# Me507Project.net
KiCad netlist of a schematic drawn in EAGLE
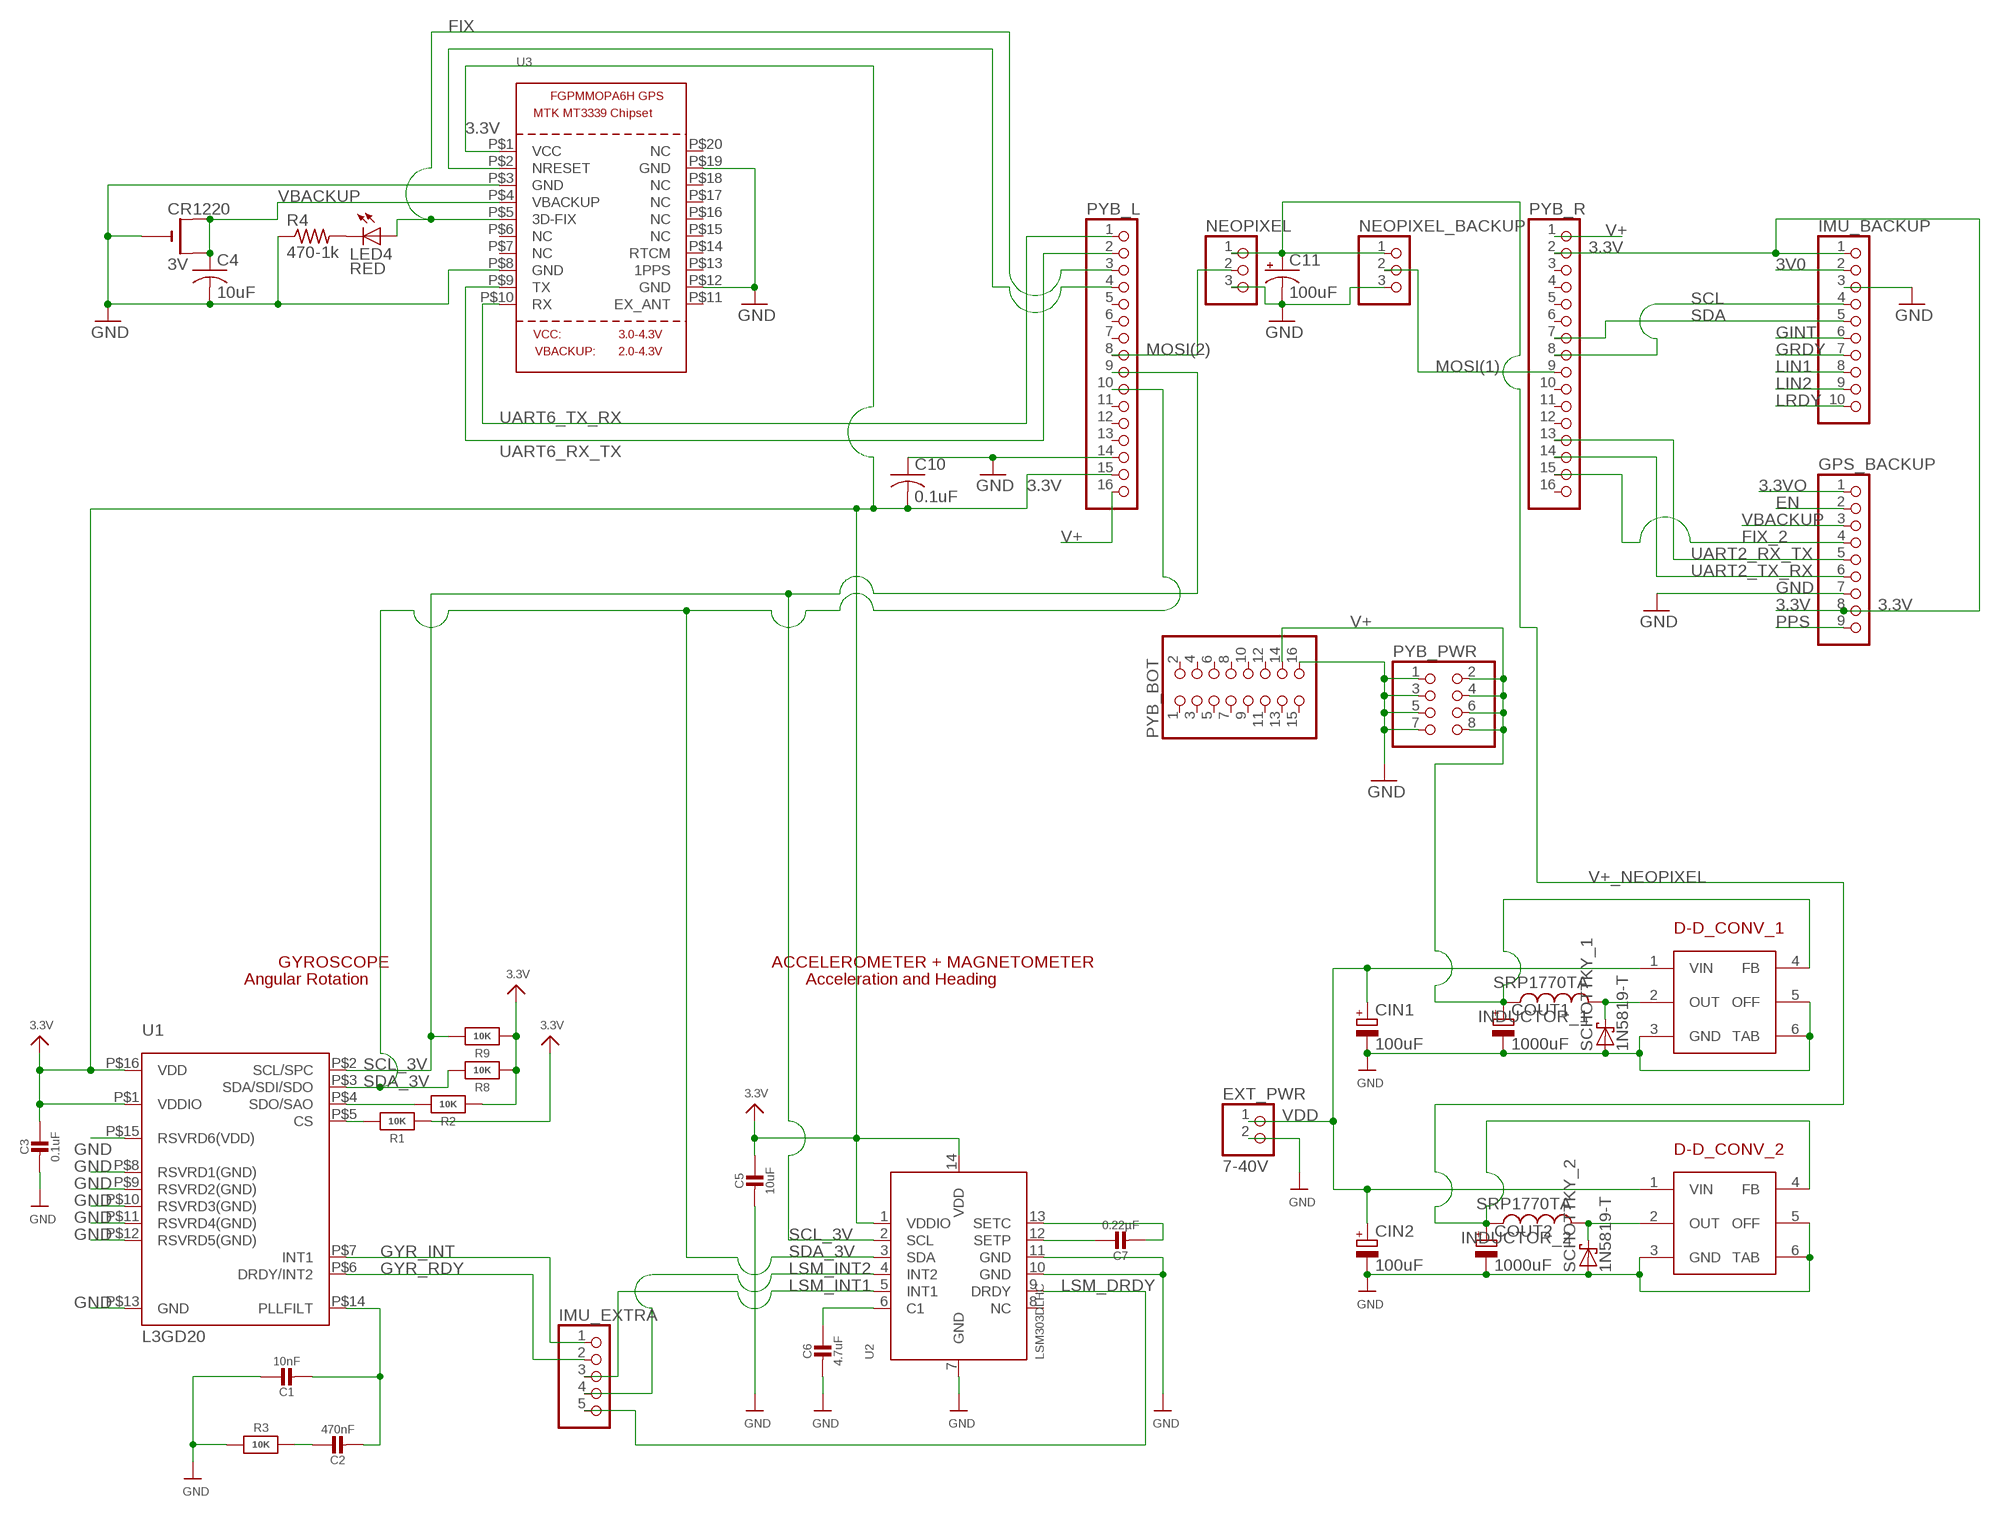
[diagram p0: schematic, sheet 1]

(export (version "E")
  (design (tool "Eeschema 10.0.6"))
  (components
    (comp (ref "C1")
      (value "10nF")
      (footprint "eagle-import:_0805MP")
      (libsource (lib "eagle-import") (part "CAP_CERAMIC_0805MP"))
    )
    (comp (ref "C2")
      (value "470nF")
      (footprint "eagle-import:_0805MP")
      (libsource (lib "eagle-import") (part "CAP_CERAMIC_0805MP"))
    )
    (comp (ref "C3")
      (value "0.1uF")
      (footprint "eagle-import:_0805MP")
      (libsource (lib "eagle-import") (part "CAP_CERAMIC_0805MP"))
    )
    (comp (ref "C4")
      (value "10uF")
      (footprint "eagle-import:C0805K")
      (libsource (lib "eagle-import") (part "C-USC0805K"))
    )
    (comp (ref "C5")
      (value "10uF")
      (footprint "eagle-import:_0805MP")
      (libsource (lib "eagle-import") (part "CAP_CERAMIC_0805MP"))
    )
    (comp (ref "C6")
      (value "4.7uF")
      (footprint "eagle-import:_0805MP")
      (libsource (lib "eagle-import") (part "CAP_CERAMIC_0805MP"))
    )
    (comp (ref "C7")
      (value "0.22µF")
      (footprint "eagle-import:_0805MP")
      (libsource (lib "eagle-import") (part "CAP_CERAMIC_0805MP"))
    )
    (comp (ref "C10")
      (value "0.1uF")
      (footprint "eagle-import:C0805K")
      (libsource (lib "eagle-import") (part "C-USC0805K"))
    )
    (comp (ref "C11")
      (value "100uF")
      (footprint "eagle-import:153CLV-0810")
      (libsource (lib "eagle-import") (part "CPOL-US153CLV-0810"))
    )
    (comp (ref "CIN1")
      (value "100uF")
      (footprint "eagle-import:UD-8X10_NICHICON")
      (libsource (lib "eagle-import") (part "CPOL-EUUD-8X10"))
    )
    (comp (ref "CIN2")
      (value "100uF")
      (footprint "eagle-import:UD-8X10_NICHICON")
      (libsource (lib "eagle-import") (part "CPOL-EUUD-8X10"))
    )
    (comp (ref "COUT1")
      (value "1000uF")
      (footprint "eagle-import:E5-13")
      (libsource (lib "eagle-import") (part "CPOL-EUE5-13"))
    )
    (comp (ref "COUT2")
      (value "1000uF")
      (footprint "eagle-import:E5-13")
      (libsource (lib "eagle-import") (part "CPOL-EUE5-13"))
    )
    (comp (ref "CR1220")
      (value "3V")
      (footprint "eagle-import:CR1220-SMD")
      (libsource (lib "eagle-import") (part "CR1220SMT"))
    )
    (comp (ref "D-D_CONV_1")
      (value "AP3003")
      (footprint "eagle-import:TO263-5")
      (libsource (lib "eagle-import") (part "AP3003"))
    )
    (comp (ref "D-D_CONV_2")
      (value "AP3003")
      (footprint "eagle-import:TO263-5")
      (libsource (lib "eagle-import") (part "AP3003"))
    )
    (comp (ref "EXT_PWR")
      (value "7-40V")
      (footprint "eagle-import:1X02")
      (libsource (lib "eagle-import") (part "PINHD-1X2"))
    )
    (comp (ref "GPS_BACKUP")
      (value "PINHD-1X9")
      (footprint "eagle-import:1X09")
      (libsource (lib "eagle-import") (part "PINHD-1X9"))
    )
    (comp (ref "IMU_BACKUP")
      (value "PINHD-1X10")
      (footprint "eagle-import:1X10")
      (libsource (lib "eagle-import") (part "PINHD-1X10"))
    )
    (comp (ref "IMU_EXTRA")
      (value "PINHD-1X5")
      (footprint "eagle-import:1X05")
      (libsource (lib "eagle-import") (part "PINHD-1X5"))
    )
    (comp (ref "INDUCTOR_1")
      (value "SRP1770TA")
      (footprint "eagle-import:SRP1770TA")
      (libsource (lib "eagle-import") (part "SRP1770TA"))
    )
    (comp (ref "INDUCTOR_2")
      (value "SRP1770TA")
      (footprint "eagle-import:SRP1770TA")
      (libsource (lib "eagle-import") (part "SRP1770TA"))
    )
    (comp (ref "LED4")
      (value "RED")
      (footprint "eagle-import:CHIP-LED0805")
      (libsource (lib "eagle-import") (part "LEDCHIP-LED0805"))
    )
    (comp (ref "NEOPIXEL")
      (value "PINHD-1X3")
      (footprint "eagle-import:1X03")
      (libsource (lib "eagle-import") (part "PINHD-1X3"))
    )
    (comp (ref "NEOPIXEL_BACKUP")
      (value "PINHD-1X3")
      (footprint "eagle-import:1X03")
      (libsource (lib "eagle-import") (part "PINHD-1X3"))
    )
    (comp (ref "PYB_BOT")
      (value "PINHD-2X8")
      (footprint "eagle-import:2X08")
      (libsource (lib "eagle-import") (part "PINHD-2X8"))
    )
    (comp (ref "PYB_L")
      (value "PINHD-1X16")
      (footprint "eagle-import:1X16")
      (libsource (lib "eagle-import") (part "PINHD-1X16"))
    )
    (comp (ref "PYB_PWR")
      (value "PINHD-2X4")
      (footprint "eagle-import:2X04")
      (libsource (lib "eagle-import") (part "PINHD-2X4"))
    )
    (comp (ref "PYB_R")
      (value "PINHD-1X16")
      (footprint "eagle-import:1X16")
      (libsource (lib "eagle-import") (part "PINHD-1X16"))
    )
    (comp (ref "R1")
      (value "10K")
      (footprint "eagle-import:_0805MP")
      (libsource (lib "eagle-import") (part "RESISTOR_0805MP"))
    )
    (comp (ref "R2")
      (value "10K")
      (footprint "eagle-import:_0805MP")
      (libsource (lib "eagle-import") (part "RESISTOR_0805MP"))
    )
    (comp (ref "R3")
      (value "10K")
      (footprint "eagle-import:_0805MP")
      (libsource (lib "eagle-import") (part "RESISTOR_0805MP"))
    )
    (comp (ref "R4")
      (value "470-1k")
      (footprint "eagle-import:R0805")
      (libsource (lib "eagle-import") (part "R-US_R0805"))
    )
    (comp (ref "R8")
      (value "10K")
      (footprint "eagle-import:_0805MP")
      (libsource (lib "eagle-import") (part "RESISTOR_0805MP"))
    )
    (comp (ref "R9")
      (value "10K")
      (footprint "eagle-import:_0805MP")
      (libsource (lib "eagle-import") (part "RESISTOR_0805MP"))
    )
    (comp (ref "SCHOTTKY_1")
      (value "1N5819-T")
      (footprint "eagle-import:DO41-7.6")
      (libsource (lib "eagle-import") (part "1N5819-T"))
    )
    (comp (ref "SCHOTTKY_2")
      (value "1N5819-T")
      (footprint "eagle-import:DO41-7.6")
      (libsource (lib "eagle-import") (part "1N5819-T"))
    )
    (comp (ref "U1")
      (value "L3GD20")
      (footprint "eagle-import:L3G4200D_LGA16L")
      (libsource (lib "eagle-import") (part "GYRO_L3G2400D"))
    )
    (comp (ref "U2")
      (value "LSM303DLHC")
      (footprint "eagle-import:LGA14")
      (libsource (lib "eagle-import") (part "LSM303DLHC"))
    )
    (comp (ref "U3")
      (value "GPS_FGPMMOPA6H")
      (footprint "eagle-import:FGPMMOPA6H")
      (libsource (lib "eagle-import") (part "GPS_FGPMMOPA6H"))
    )
  )
  (nets
    (net (code "1") (name "/3.3VO") (class "Default")
      (node (ref "GPS_BACKUP") (pin "1") (pinfunction "1_1") (pintype "passive"))
    )
    (net (code "2") (name "/3V0") (class "Default")
      (node (ref "IMU_BACKUP") (pin "2") (pinfunction "2_2") (pintype "passive"))
    )
    (net (code "3") (name "/EN") (class "Default")
      (node (ref "GPS_BACKUP") (pin "2") (pinfunction "2_2") (pintype "passive"))
    )
    (net (code "4") (name "/FIX") (class "Default")
      (node (ref "LED4") (pin "A") (pinfunction "A_A") (pintype "passive"))
      (node (ref "PYB_L") (pin "3") (pinfunction "3_3") (pintype "passive"))
      (node (ref "U3") (pin "P$5") (pinfunction "3D-FIX_P$5") (pintype "bidirectional"))
    )
    (net (code "5") (name "/FIX_2") (class "Default")
      (node (ref "GPS_BACKUP") (pin "4") (pinfunction "4_4") (pintype "passive"))
      (node (ref "PYB_R") (pin "15") (pinfunction "15_15") (pintype "passive"))
    )
    (net (code "6") (name "/GINT") (class "Default")
      (node (ref "IMU_BACKUP") (pin "6") (pinfunction "6_6") (pintype "passive"))
    )
    (net (code "7") (name "/GRDY") (class "Default")
      (node (ref "IMU_BACKUP") (pin "7") (pinfunction "7_7") (pintype "passive"))
    )
    (net (code "8") (name "/GYR_INT") (class "Default")
      (node (ref "IMU_EXTRA") (pin "1") (pinfunction "1_1") (pintype "passive"))
      (node (ref "U1") (pin "P$7") (pinfunction "INT1_P$7") (pintype "bidirectional"))
    )
    (net (code "9") (name "/GYR_RDY") (class "Default")
      (node (ref "IMU_EXTRA") (pin "2") (pinfunction "2_2") (pintype "passive"))
      (node (ref "U1") (pin "P$6") (pinfunction "DRDY/INT2_P$6") (pintype "bidirectional"))
    )
    (net (code "10") (name "/LIN1") (class "Default")
      (node (ref "IMU_BACKUP") (pin "8") (pinfunction "8_8") (pintype "passive"))
    )
    (net (code "11") (name "/LIN2") (class "Default")
      (node (ref "IMU_BACKUP") (pin "9") (pinfunction "9_9") (pintype "passive"))
    )
    (net (code "12") (name "/LRDY") (class "Default")
      (node (ref "IMU_BACKUP") (pin "10") (pinfunction "10_10") (pintype "passive"))
    )
    (net (code "13") (name "/LSM_DRDY") (class "Default")
      (node (ref "IMU_EXTRA") (pin "5") (pinfunction "5_5") (pintype "passive"))
      (node (ref "U2") (pin "9") (pinfunction "DRDY_9") (pintype "output"))
    )
    (net (code "14") (name "/LSM_INT1") (class "Default")
      (node (ref "IMU_EXTRA") (pin "3") (pinfunction "3_3") (pintype "passive"))
      (node (ref "U2") (pin "5") (pinfunction "INT1_5") (pintype "output"))
    )
    (net (code "15") (name "/LSM_INT2") (class "Default")
      (node (ref "IMU_EXTRA") (pin "4") (pinfunction "4_4") (pintype "passive"))
      (node (ref "U2") (pin "4") (pinfunction "INT2_4") (pintype "output"))
    )
    (net (code "16") (name "/MOSI(1)") (class "Default")
      (node (ref "NEOPIXEL_BACKUP") (pin "2") (pinfunction "2_2") (pintype "passive"))
      (node (ref "PYB_R") (pin "9") (pinfunction "9_9") (pintype "passive"))
    )
    (net (code "17") (name "/MOSI(2)") (class "Default")
      (node (ref "NEOPIXEL") (pin "2") (pinfunction "2_2") (pintype "passive"))
      (node (ref "PYB_L") (pin "8") (pinfunction "8_8") (pintype "passive"))
    )
    (net (code "18") (name "/PPS") (class "Default")
      (node (ref "GPS_BACKUP") (pin "9") (pinfunction "9_9") (pintype "passive"))
    )
    (net (code "19") (name "/SCL") (class "Default")
      (node (ref "IMU_BACKUP") (pin "4") (pinfunction "4_4") (pintype "passive"))
      (node (ref "PYB_R") (pin "8") (pinfunction "8_8") (pintype "passive"))
    )
    (net (code "20") (name "/SCL_3V") (class "Default")
      (node (ref "PYB_L") (pin "9") (pinfunction "9_9") (pintype "passive"))
      (node (ref "R9") (pin "2") (pinfunction "2_2") (pintype "passive"))
      (node (ref "U1") (pin "P$2") (pinfunction "SCL/SPC_P$2") (pintype "bidirectional"))
      (node (ref "U2") (pin "2") (pinfunction "SCL_2") (pintype "bidirectional"))
    )
    (net (code "21") (name "/SDA") (class "Default")
      (node (ref "IMU_BACKUP") (pin "5") (pinfunction "5_5") (pintype "passive"))
      (node (ref "PYB_R") (pin "7") (pinfunction "7_7") (pintype "passive"))
    )
    (net (code "22") (name "/SDA_3V") (class "Default")
      (node (ref "PYB_L") (pin "10") (pinfunction "10_10") (pintype "passive"))
      (node (ref "R8") (pin "2") (pinfunction "2_2") (pintype "passive"))
      (node (ref "U1") (pin "P$3") (pinfunction "SDA/SDI/SDO_P$3") (pintype "bidirectional"))
      (node (ref "U2") (pin "3") (pinfunction "SDA_3") (pintype "bidirectional"))
    )
    (net (code "23") (name "/UART2_RX_TX") (class "Default")
      (node (ref "GPS_BACKUP") (pin "5") (pinfunction "5_5") (pintype "passive"))
      (node (ref "PYB_R") (pin "13") (pinfunction "13_13") (pintype "passive"))
    )
    (net (code "24") (name "/UART2_TX_RX") (class "Default")
      (node (ref "GPS_BACKUP") (pin "6") (pinfunction "6_6") (pintype "passive"))
      (node (ref "PYB_R") (pin "14") (pinfunction "14_14") (pintype "passive"))
    )
    (net (code "25") (name "/UART6_RX_TX") (class "Default")
      (node (ref "PYB_L") (pin "2") (pinfunction "2_2") (pintype "passive"))
      (node (ref "U3") (pin "P$9") (pinfunction "TX_P$9") (pintype "bidirectional"))
    )
    (net (code "26") (name "/UART6_TX_RX") (class "Default")
      (node (ref "PYB_L") (pin "1") (pinfunction "1_1") (pintype "passive"))
      (node (ref "U3") (pin "P$10") (pinfunction "RX_P$10") (pintype "bidirectional"))
    )
    (net (code "27") (name "/V+") (class "Default")
      (node (ref "COUT1") (pin "+") (pinfunction "+_+") (pintype "passive"))
      (node (ref "D-D_CONV_1") (pin "4") (pinfunction "FB_4") (pintype "bidirectional"))
      (node (ref "INDUCTOR_1") (pin "P$3") (pinfunction "1_P$3") (pintype "passive"))
      (node (ref "PYB_BOT") (pin "14") (pinfunction "14_14") (pintype "passive"))
      (node (ref "PYB_L") (pin "16") (pinfunction "16_16") (pintype "passive"))
      (node (ref "PYB_PWR") (pin "2") (pinfunction "2_2") (pintype "passive"))
      (node (ref "PYB_PWR") (pin "4") (pinfunction "4_4") (pintype "passive"))
      (node (ref "PYB_PWR") (pin "6") (pinfunction "6_6") (pintype "passive"))
      (node (ref "PYB_PWR") (pin "8") (pinfunction "8_8") (pintype "passive"))
      (node (ref "PYB_R") (pin "1") (pinfunction "1_1") (pintype "passive"))
    )
    (net (code "28") (name "/V+_NEOPIXEL") (class "Default")
      (node (ref "C11") (pin "+") (pinfunction "+_+") (pintype "passive"))
      (node (ref "COUT2") (pin "+") (pinfunction "+_+") (pintype "passive"))
      (node (ref "D-D_CONV_2") (pin "4") (pinfunction "FB_4") (pintype "bidirectional"))
      (node (ref "INDUCTOR_2") (pin "P$3") (pinfunction "1_P$3") (pintype "passive"))
      (node (ref "NEOPIXEL") (pin "1") (pinfunction "1_1") (pintype "passive"))
      (node (ref "NEOPIXEL_BACKUP") (pin "1") (pinfunction "1_1") (pintype "passive"))
    )
    (net (code "29") (name "/VBACKUP") (class "Default")
      (node (ref "C4") (pin "1") (pinfunction "1_1") (pintype "passive"))
      (node (ref "CR1220") (pin "+$1") (pinfunction "+_+$1") (pintype "passive"))
      (node (ref "CR1220") (pin "+$2") (pinfunction "+1_+$2") (pintype "passive"))
      (node (ref "GPS_BACKUP") (pin "3") (pinfunction "3_3") (pintype "passive"))
      (node (ref "U3") (pin "P$4") (pinfunction "VBACKUP_P$4") (pintype "bidirectional"))
    )
    (net (code "30") (name "/VDD") (class "Default")
      (node (ref "CIN1") (pin "+") (pinfunction "+_+") (pintype "passive"))
      (node (ref "CIN2") (pin "+") (pinfunction "+_+") (pintype "passive"))
      (node (ref "D-D_CONV_1") (pin "1") (pinfunction "VIN_1") (pintype "bidirectional"))
      (node (ref "D-D_CONV_2") (pin "1") (pinfunction "VIN_1") (pintype "bidirectional"))
      (node (ref "EXT_PWR") (pin "1") (pinfunction "1_1") (pintype "passive"))
    )
    (net (code "31") (name "3.3V") (class "Default")
      (node (ref "C10") (pin "2") (pinfunction "2_2") (pintype "passive"))
      (node (ref "C3") (pin "1") (pinfunction "1_1") (pintype "passive"))
      (node (ref "C5") (pin "1") (pinfunction "1_1") (pintype "passive"))
      (node (ref "GPS_BACKUP") (pin "8") (pinfunction "8_8") (pintype "passive"))
      (node (ref "IMU_BACKUP") (pin "1") (pinfunction "1_1") (pintype "passive"))
      (node (ref "PYB_L") (pin "15") (pinfunction "15_15") (pintype "passive"))
      (node (ref "PYB_R") (pin "2") (pinfunction "2_2") (pintype "passive"))
      (node (ref "R1") (pin "1") (pinfunction "1_1") (pintype "passive"))
      (node (ref "R2") (pin "1") (pinfunction "1_1") (pintype "passive"))
      (node (ref "R8") (pin "1") (pinfunction "1_1") (pintype "passive"))
      (node (ref "R9") (pin "1") (pinfunction "1_1") (pintype "passive"))
      (node (ref "U1") (pin "P$1") (pinfunction "VDDIO_P$1") (pintype "power_in"))
      (node (ref "U1") (pin "P$16") (pinfunction "VDD_P$16") (pintype "bidirectional"))
      (node (ref "U2") (pin "1") (pinfunction "VDDIO_1") (pintype "power_in"))
      (node (ref "U2") (pin "14") (pinfunction "VDD_14") (pintype "power_in"))
      (node (ref "U3") (pin "P$1") (pinfunction "VCC_P$1") (pintype "bidirectional"))
    )
    (net (code "32") (name "GND") (class "Default")
      (node (ref "C1") (pin "1") (pinfunction "1_1") (pintype "passive"))
      (node (ref "C10") (pin "1") (pinfunction "1_1") (pintype "passive"))
      (node (ref "C11") (pin "-") (pinfunction "-_-") (pintype "passive"))
      (node (ref "C3") (pin "2") (pinfunction "2_2") (pintype "passive"))
      (node (ref "C4") (pin "2") (pinfunction "2_2") (pintype "passive"))
      (node (ref "C5") (pin "2") (pinfunction "2_2") (pintype "passive"))
      (node (ref "C6") (pin "2") (pinfunction "2_2") (pintype "passive"))
      (node (ref "CIN1") (pin "-") (pinfunction "-_-") (pintype "passive"))
      (node (ref "CIN2") (pin "-") (pinfunction "-_-") (pintype "passive"))
      (node (ref "COUT1") (pin "-") (pinfunction "-_-") (pintype "passive"))
      (node (ref "COUT2") (pin "-") (pinfunction "-_-") (pintype "passive"))
      (node (ref "CR1220") (pin "-") (pinfunction "-_-") (pintype "passive"))
      (node (ref "D-D_CONV_1") (pin "3") (pinfunction "GND_3") (pintype "bidirectional"))
      (node (ref "D-D_CONV_1") (pin "5") (pinfunction "OFF_5") (pintype "bidirectional"))
      (node (ref "D-D_CONV_1") (pin "6") (pinfunction "TAB_6") (pintype "bidirectional"))
      (node (ref "D-D_CONV_2") (pin "3") (pinfunction "GND_3") (pintype "bidirectional"))
      (node (ref "D-D_CONV_2") (pin "5") (pinfunction "OFF_5") (pintype "bidirectional"))
      (node (ref "D-D_CONV_2") (pin "6") (pinfunction "TAB_6") (pintype "bidirectional"))
      (node (ref "EXT_PWR") (pin "2") (pinfunction "2_2") (pintype "passive"))
      (node (ref "GPS_BACKUP") (pin "7") (pinfunction "7_7") (pintype "passive"))
      (node (ref "IMU_BACKUP") (pin "3") (pinfunction "3_3") (pintype "passive"))
      (node (ref "NEOPIXEL") (pin "3") (pinfunction "3_3") (pintype "passive"))
      (node (ref "NEOPIXEL_BACKUP") (pin "3") (pinfunction "3_3") (pintype "passive"))
      (node (ref "PYB_BOT") (pin "16") (pinfunction "16_16") (pintype "passive"))
      (node (ref "PYB_L") (pin "14") (pinfunction "14_14") (pintype "passive"))
      (node (ref "PYB_PWR") (pin "1") (pinfunction "1_1") (pintype "passive"))
      (node (ref "PYB_PWR") (pin "3") (pinfunction "3_3") (pintype "passive"))
      (node (ref "PYB_PWR") (pin "5") (pinfunction "5_5") (pintype "passive"))
      (node (ref "PYB_PWR") (pin "7") (pinfunction "7_7") (pintype "passive"))
      (node (ref "R3") (pin "1") (pinfunction "1_1") (pintype "passive"))
      (node (ref "R4") (pin "1") (pinfunction "1_1") (pintype "passive"))
      (node (ref "SCHOTTKY_1") (pin "A") (pinfunction "A_A") (pintype "passive"))
      (node (ref "SCHOTTKY_2") (pin "A") (pinfunction "A_A") (pintype "passive"))
      (node (ref "U1") (pin "P$10") (pinfunction "RSVRD3(GND)_P$10") (pintype "bidirectional"))
      (node (ref "U1") (pin "P$11") (pinfunction "RSVRD4(GND)_P$11") (pintype "bidirectional"))
      (node (ref "U1") (pin "P$12") (pinfunction "RSVRD5(GND)_P$12") (pintype "bidirectional"))
      (node (ref "U1") (pin "P$13") (pinfunction "GND_P$13") (pintype "bidirectional"))
      (node (ref "U1") (pin "P$15") (pinfunction "RSVRD6(VDD)_P$15") (pintype "bidirectional"))
      (node (ref "U1") (pin "P$8") (pinfunction "RSVRD1(GND)_P$8") (pintype "bidirectional"))
      (node (ref "U1") (pin "P$9") (pinfunction "RSVRD2(GND)_P$9") (pintype "bidirectional"))
      (node (ref "U2") (pin "10") (pinfunction "GND_10") (pintype "power_in"))
      (node (ref "U2") (pin "11") (pinfunction "GND_11") (pintype "power_in"))
      (node (ref "U2") (pin "7") (pinfunction "GND_7") (pintype "power_in"))
      (node (ref "U3") (pin "P$12") (pinfunction "GND_P$12") (pintype "bidirectional"))
      (node (ref "U3") (pin "P$19") (pinfunction "GND_P$19") (pintype "bidirectional"))
      (node (ref "U3") (pin "P$3") (pinfunction "GND_P$3") (pintype "bidirectional"))
      (node (ref "U3") (pin "P$8") (pinfunction "GND_P$8") (pintype "bidirectional"))
    )
    (net (code "33") (name "Net-(C2-Pad1)") (class "Default")
      (node (ref "C2") (pin "1") (pinfunction "1_1") (pintype "passive"))
      (node (ref "R3") (pin "2") (pinfunction "2_2") (pintype "passive"))
    )
    (net (code "34") (name "Net-(D-D_CONV_1-OUT)") (class "Default")
      (node (ref "D-D_CONV_1") (pin "2") (pinfunction "OUT_2") (pintype "bidirectional"))
      (node (ref "INDUCTOR_1") (pin "P$4") (pinfunction "2_P$4") (pintype "passive"))
      (node (ref "SCHOTTKY_1") (pin "C") (pinfunction "C_C") (pintype "passive"))
    )
    (net (code "35") (name "Net-(D-D_CONV_2-OUT)") (class "Default")
      (node (ref "D-D_CONV_2") (pin "2") (pinfunction "OUT_2") (pintype "bidirectional"))
      (node (ref "INDUCTOR_2") (pin "P$4") (pinfunction "2_P$4") (pintype "passive"))
      (node (ref "SCHOTTKY_2") (pin "C") (pinfunction "C_C") (pintype "passive"))
    )
    (net (code "36") (name "Net-(LED4-PadC)") (class "Default")
      (node (ref "LED4") (pin "C") (pinfunction "C_C") (pintype "passive"))
      (node (ref "R4") (pin "2") (pinfunction "2_2") (pintype "passive"))
    )
    (net (code "37") (name "Net-(U1-CS)") (class "Default")
      (node (ref "R1") (pin "2") (pinfunction "2_2") (pintype "passive"))
      (node (ref "U1") (pin "P$5") (pinfunction "CS_P$5") (pintype "bidirectional"))
    )
    (net (code "38") (name "Net-(U1-PLLFILT)") (class "Default")
      (node (ref "C1") (pin "2") (pinfunction "2_2") (pintype "passive"))
      (node (ref "C2") (pin "2") (pinfunction "2_2") (pintype "passive"))
      (node (ref "U1") (pin "P$14") (pinfunction "PLLFILT_P$14") (pintype "bidirectional"))
    )
    (net (code "39") (name "Net-(U1-SDO{slash}SAO)") (class "Default")
      (node (ref "R2") (pin "2") (pinfunction "2_2") (pintype "passive"))
      (node (ref "U1") (pin "P$4") (pinfunction "SDO/SAO_P$4") (pintype "bidirectional"))
    )
    (net (code "40") (name "Net-(U2-C1)") (class "Default")
      (node (ref "C6") (pin "1") (pinfunction "1_1") (pintype "passive"))
      (node (ref "U2") (pin "6") (pinfunction "C1_6") (pintype "bidirectional"))
    )
    (net (code "41") (name "Net-(U2-SETC)") (class "Default")
      (node (ref "C7") (pin "2") (pinfunction "2_2") (pintype "passive"))
      (node (ref "U2") (pin "13") (pinfunction "SETC_13") (pintype "bidirectional"))
    )
    (net (code "42") (name "Net-(U2-SETP)") (class "Default")
      (node (ref "C7") (pin "1") (pinfunction "1_1") (pintype "passive"))
      (node (ref "U2") (pin "12") (pinfunction "SETP_12") (pintype "bidirectional"))
    )
    (net (code "43") (name "Net-(U3-NRESET)") (class "Default")
      (node (ref "PYB_L") (pin "4") (pinfunction "4_4") (pintype "passive"))
      (node (ref "U3") (pin "P$2") (pinfunction "NRESET_P$2") (pintype "bidirectional"))
    )
    (net (code "44") (name "unconnected-(PYB_BOT-Pad1)") (class "Default")
      (node (ref "PYB_BOT") (pin "1") (pinfunction "1_1") (pintype "passive"))
    )
    (net (code "45") (name "unconnected-(PYB_BOT-Pad2)") (class "Default")
      (node (ref "PYB_BOT") (pin "2") (pinfunction "2_2") (pintype "passive"))
    )
    (net (code "46") (name "unconnected-(PYB_BOT-Pad3)") (class "Default")
      (node (ref "PYB_BOT") (pin "3") (pinfunction "3_3") (pintype "passive"))
    )
    (net (code "47") (name "unconnected-(PYB_BOT-Pad4)") (class "Default")
      (node (ref "PYB_BOT") (pin "4") (pinfunction "4_4") (pintype "passive"))
    )
    (net (code "48") (name "unconnected-(PYB_BOT-Pad5)") (class "Default")
      (node (ref "PYB_BOT") (pin "5") (pinfunction "5_5") (pintype "passive"))
    )
    (net (code "49") (name "unconnected-(PYB_BOT-Pad6)") (class "Default")
      (node (ref "PYB_BOT") (pin "6") (pinfunction "6_6") (pintype "passive"))
    )
    (net (code "50") (name "unconnected-(PYB_BOT-Pad7)") (class "Default")
      (node (ref "PYB_BOT") (pin "7") (pinfunction "7_7") (pintype "passive"))
    )
    (net (code "51") (name "unconnected-(PYB_BOT-Pad8)") (class "Default")
      (node (ref "PYB_BOT") (pin "8") (pinfunction "8_8") (pintype "passive"))
    )
    (net (code "52") (name "unconnected-(PYB_BOT-Pad9)") (class "Default")
      (node (ref "PYB_BOT") (pin "9") (pinfunction "9_9") (pintype "passive"))
    )
    (net (code "53") (name "unconnected-(PYB_BOT-Pad10)") (class "Default")
      (node (ref "PYB_BOT") (pin "10") (pinfunction "10_10") (pintype "passive"))
    )
    (net (code "54") (name "unconnected-(PYB_BOT-Pad11)") (class "Default")
      (node (ref "PYB_BOT") (pin "11") (pinfunction "11_11") (pintype "passive"))
    )
    (net (code "55") (name "unconnected-(PYB_BOT-Pad12)") (class "Default")
      (node (ref "PYB_BOT") (pin "12") (pinfunction "12_12") (pintype "passive"))
    )
    (net (code "56") (name "unconnected-(PYB_BOT-Pad13)") (class "Default")
      (node (ref "PYB_BOT") (pin "13") (pinfunction "13_13") (pintype "passive"))
    )
    (net (code "57") (name "unconnected-(PYB_BOT-Pad15)") (class "Default")
      (node (ref "PYB_BOT") (pin "15") (pinfunction "15_15") (pintype "passive"))
    )
    (net (code "58") (name "unconnected-(PYB_L-Pad5)") (class "Default")
      (node (ref "PYB_L") (pin "5") (pinfunction "5_5") (pintype "passive"))
    )
    (net (code "59") (name "unconnected-(PYB_L-Pad6)") (class "Default")
      (node (ref "PYB_L") (pin "6") (pinfunction "6_6") (pintype "passive"))
    )
    (net (code "60") (name "unconnected-(PYB_L-Pad7)") (class "Default")
      (node (ref "PYB_L") (pin "7") (pinfunction "7_7") (pintype "passive"))
    )
    (net (code "61") (name "unconnected-(PYB_L-Pad11)") (class "Default")
      (node (ref "PYB_L") (pin "11") (pinfunction "11_11") (pintype "passive"))
    )
    (net (code "62") (name "unconnected-(PYB_L-Pad12)") (class "Default")
      (node (ref "PYB_L") (pin "12") (pinfunction "12_12") (pintype "passive"))
    )
    (net (code "63") (name "unconnected-(PYB_L-Pad13)") (class "Default")
      (node (ref "PYB_L") (pin "13") (pinfunction "13_13") (pintype "passive"))
    )
    (net (code "64") (name "unconnected-(PYB_R-Pad3)") (class "Default")
      (node (ref "PYB_R") (pin "3") (pinfunction "3_3") (pintype "passive"))
    )
    (net (code "65") (name "unconnected-(PYB_R-Pad4)") (class "Default")
      (node (ref "PYB_R") (pin "4") (pinfunction "4_4") (pintype "passive"))
    )
    (net (code "66") (name "unconnected-(PYB_R-Pad5)") (class "Default")
      (node (ref "PYB_R") (pin "5") (pinfunction "5_5") (pintype "passive"))
    )
    (net (code "67") (name "unconnected-(PYB_R-Pad6)") (class "Default")
      (node (ref "PYB_R") (pin "6") (pinfunction "6_6") (pintype "passive"))
    )
    (net (code "68") (name "unconnected-(PYB_R-Pad10)") (class "Default")
      (node (ref "PYB_R") (pin "10") (pinfunction "10_10") (pintype "passive"))
    )
    (net (code "69") (name "unconnected-(PYB_R-Pad11)") (class "Default")
      (node (ref "PYB_R") (pin "11") (pinfunction "11_11") (pintype "passive"))
    )
    (net (code "70") (name "unconnected-(PYB_R-Pad12)") (class "Default")
      (node (ref "PYB_R") (pin "12") (pinfunction "12_12") (pintype "passive"))
    )
    (net (code "71") (name "unconnected-(PYB_R-Pad16)") (class "Default")
      (node (ref "PYB_R") (pin "16") (pinfunction "16_16") (pintype "passive"))
    )
    (net (code "72") (name "unconnected-(U2-NC-Pad8)") (class "Default")
      (node (ref "U2") (pin "8") (pinfunction "NC_8") (pintype "bidirectional"))
    )
    (net (code "73") (name "unconnected-(U3-1PPS-PadP$13)") (class "Default")
      (node (ref "U3") (pin "P$13") (pinfunction "1PPS_P$13") (pintype "bidirectional"))
    )
    (net (code "74") (name "unconnected-(U3-EX_ANT-PadP$11)") (class "Default")
      (node (ref "U3") (pin "P$11") (pinfunction "EX_ANT_P$11") (pintype "bidirectional"))
    )
    (net (code "75") (name "unconnected-(U3-NC-PadP$6)") (class "Default")
      (node (ref "U3") (pin "P$6") (pinfunction "NC_P$6") (pintype "bidirectional"))
    )
    (net (code "76") (name "unconnected-(U3-NC-PadP$7)") (class "Default")
      (node (ref "U3") (pin "P$7") (pinfunction "NC_P$7") (pintype "bidirectional"))
    )
    (net (code "77") (name "unconnected-(U3-NC-PadP$15)") (class "Default")
      (node (ref "U3") (pin "P$15") (pinfunction "NC_P$15") (pintype "bidirectional"))
    )
    (net (code "78") (name "unconnected-(U3-NC-PadP$16)") (class "Default")
      (node (ref "U3") (pin "P$16") (pinfunction "NC_P$16") (pintype "bidirectional"))
    )
    (net (code "79") (name "unconnected-(U3-NC-PadP$17)") (class "Default")
      (node (ref "U3") (pin "P$17") (pinfunction "NC_P$17") (pintype "bidirectional"))
    )
    (net (code "80") (name "unconnected-(U3-NC-PadP$18)") (class "Default")
      (node (ref "U3") (pin "P$18") (pinfunction "NC_P$18") (pintype "bidirectional"))
    )
    (net (code "81") (name "unconnected-(U3-NC-PadP$20)") (class "Default")
      (node (ref "U3") (pin "P$20") (pinfunction "NC_P$20") (pintype "bidirectional"))
    )
    (net (code "82") (name "unconnected-(U3-RTCM-PadP$14)") (class "Default")
      (node (ref "U3") (pin "P$14") (pinfunction "RTCM_P$14") (pintype "bidirectional"))
    )
  )
)
